# Memory_Chips_5_to_8.net
KiCad netlist of a schematic drawn in Altium Designer
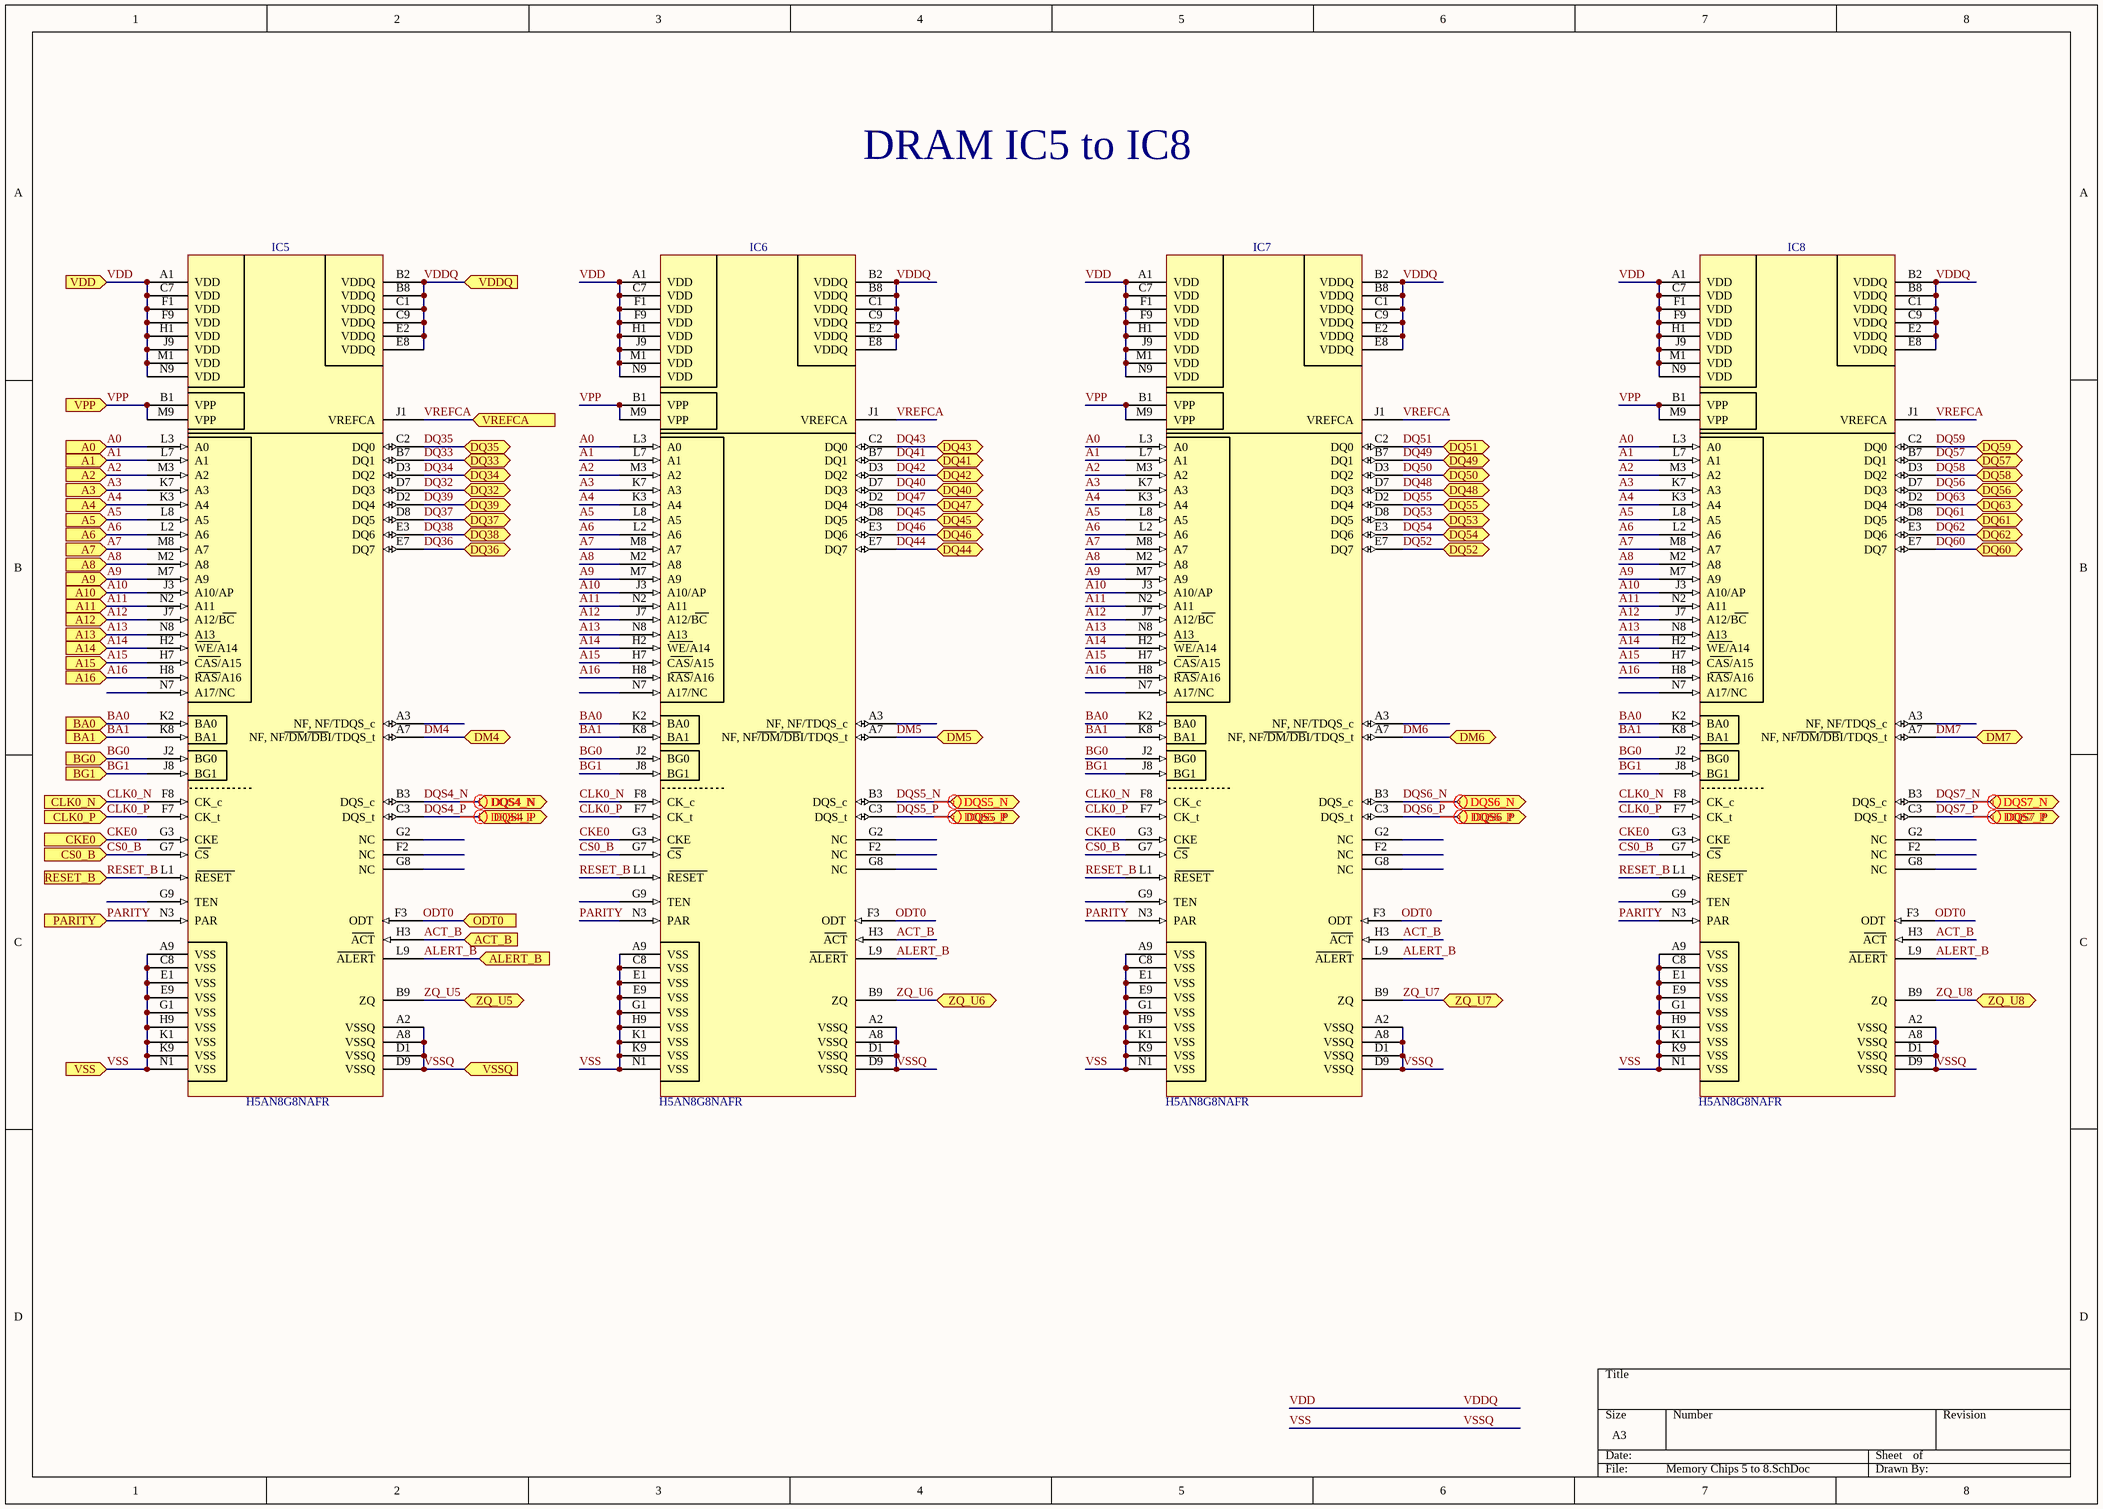
[diagram p0: Memory Chips 5 to 8.SchDoc]

(export (version "E")
  (design (tool "Eeschema 10.0.6"))
  (components
    (comp (ref "IC5")
      (value "H5AN8G8NAFR")
      (footprint "H5AN8G8NAFR")
      (libsource (lib "RouterIntLib") (part "H5AN8G8NAFR"))
    )
    (comp (ref "IC6")
      (value "H5AN8G8NAFR")
      (footprint "H5AN8G8NAFR")
      (libsource (lib "RouterIntLib") (part "H5AN8G8NAFR"))
    )
    (comp (ref "IC7")
      (value "H5AN8G8NAFR")
      (footprint "H5AN8G8NAFR")
      (libsource (lib "RouterIntLib") (part "H5AN8G8NAFR"))
    )
    (comp (ref "IC8")
      (value "H5AN8G8NAFR")
      (footprint "H5AN8G8NAFR")
      (libsource (lib "RouterIntLib") (part "H5AN8G8NAFR"))
    )
  )
  (nets
    (net (code "1") (name "/A0") (class "Default")
      (node (ref "IC5") (pin "L3") (pinfunction "A0_L3") (pintype "input"))
      (node (ref "IC6") (pin "L3") (pinfunction "A0_L3") (pintype "input"))
      (node (ref "IC7") (pin "L3") (pinfunction "A0_L3") (pintype "input"))
      (node (ref "IC8") (pin "L3") (pinfunction "A0_L3") (pintype "input"))
    )
    (net (code "2") (name "/A1") (class "Default")
      (node (ref "IC5") (pin "L7") (pinfunction "A1_L7") (pintype "input"))
      (node (ref "IC6") (pin "L7") (pinfunction "A1_L7") (pintype "input"))
      (node (ref "IC7") (pin "L7") (pinfunction "A1_L7") (pintype "input"))
      (node (ref "IC8") (pin "L7") (pinfunction "A1_L7") (pintype "input"))
    )
    (net (code "3") (name "/A2") (class "Default")
      (node (ref "IC5") (pin "M3") (pinfunction "A2_M3") (pintype "input"))
      (node (ref "IC6") (pin "M3") (pinfunction "A2_M3") (pintype "input"))
      (node (ref "IC7") (pin "M3") (pinfunction "A2_M3") (pintype "input"))
      (node (ref "IC8") (pin "M3") (pinfunction "A2_M3") (pintype "input"))
    )
    (net (code "4") (name "/A3") (class "Default")
      (node (ref "IC5") (pin "K7") (pinfunction "A3_K7") (pintype "input"))
      (node (ref "IC6") (pin "K7") (pinfunction "A3_K7") (pintype "input"))
      (node (ref "IC7") (pin "K7") (pinfunction "A3_K7") (pintype "input"))
      (node (ref "IC8") (pin "K7") (pinfunction "A3_K7") (pintype "input"))
    )
    (net (code "5") (name "/A4") (class "Default")
      (node (ref "IC5") (pin "K3") (pinfunction "A4_K3") (pintype "input"))
      (node (ref "IC6") (pin "K3") (pinfunction "A4_K3") (pintype "input"))
      (node (ref "IC7") (pin "K3") (pinfunction "A4_K3") (pintype "input"))
      (node (ref "IC8") (pin "K3") (pinfunction "A4_K3") (pintype "input"))
    )
    (net (code "6") (name "/A5") (class "Default")
      (node (ref "IC5") (pin "L8") (pinfunction "A5_L8") (pintype "input"))
      (node (ref "IC6") (pin "L8") (pinfunction "A5_L8") (pintype "input"))
      (node (ref "IC7") (pin "L8") (pinfunction "A5_L8") (pintype "input"))
      (node (ref "IC8") (pin "L8") (pinfunction "A5_L8") (pintype "input"))
    )
    (net (code "7") (name "/A6") (class "Default")
      (node (ref "IC5") (pin "L2") (pinfunction "A6_L2") (pintype "input"))
      (node (ref "IC6") (pin "L2") (pinfunction "A6_L2") (pintype "input"))
      (node (ref "IC7") (pin "L2") (pinfunction "A6_L2") (pintype "input"))
      (node (ref "IC8") (pin "L2") (pinfunction "A6_L2") (pintype "input"))
    )
    (net (code "8") (name "/A7") (class "Default")
      (node (ref "IC5") (pin "M8") (pinfunction "A7_M8") (pintype "input"))
      (node (ref "IC6") (pin "M8") (pinfunction "A7_M8") (pintype "input"))
      (node (ref "IC7") (pin "M8") (pinfunction "A7_M8") (pintype "input"))
      (node (ref "IC8") (pin "M8") (pinfunction "A7_M8") (pintype "input"))
    )
    (net (code "9") (name "/A8") (class "Default")
      (node (ref "IC5") (pin "M2") (pinfunction "A8_M2") (pintype "input"))
      (node (ref "IC6") (pin "M2") (pinfunction "A8_M2") (pintype "input"))
      (node (ref "IC7") (pin "M2") (pinfunction "A8_M2") (pintype "input"))
      (node (ref "IC8") (pin "M2") (pinfunction "A8_M2") (pintype "input"))
    )
    (net (code "10") (name "/A9") (class "Default")
      (node (ref "IC5") (pin "M7") (pinfunction "A9_M7") (pintype "input"))
      (node (ref "IC6") (pin "M7") (pinfunction "A9_M7") (pintype "input"))
      (node (ref "IC7") (pin "M7") (pinfunction "A9_M7") (pintype "input"))
      (node (ref "IC8") (pin "M7") (pinfunction "A9_M7") (pintype "input"))
    )
    (net (code "11") (name "/A10") (class "Default")
      (node (ref "IC5") (pin "J3") (pinfunction "A10/AP_J3") (pintype "input"))
      (node (ref "IC6") (pin "J3") (pinfunction "A10/AP_J3") (pintype "input"))
      (node (ref "IC7") (pin "J3") (pinfunction "A10/AP_J3") (pintype "input"))
      (node (ref "IC8") (pin "J3") (pinfunction "A10/AP_J3") (pintype "input"))
    )
    (net (code "12") (name "/A11") (class "Default")
      (node (ref "IC5") (pin "N2") (pinfunction "A11_N2") (pintype "input"))
      (node (ref "IC6") (pin "N2") (pinfunction "A11_N2") (pintype "input"))
      (node (ref "IC7") (pin "N2") (pinfunction "A11_N2") (pintype "input"))
      (node (ref "IC8") (pin "N2") (pinfunction "A11_N2") (pintype "input"))
    )
    (net (code "13") (name "/A12") (class "Default")
      (node (ref "IC5") (pin "J7") (pinfunction "A12/BC_J7") (pintype "input"))
      (node (ref "IC6") (pin "J7") (pinfunction "A12/BC_J7") (pintype "input"))
      (node (ref "IC7") (pin "J7") (pinfunction "A12/BC_J7") (pintype "input"))
      (node (ref "IC8") (pin "J7") (pinfunction "A12/BC_J7") (pintype "input"))
    )
    (net (code "14") (name "/A13") (class "Default")
      (node (ref "IC5") (pin "N8") (pinfunction "A13_N8") (pintype "input"))
      (node (ref "IC6") (pin "N8") (pinfunction "A13_N8") (pintype "input"))
      (node (ref "IC7") (pin "N8") (pinfunction "A13_N8") (pintype "input"))
      (node (ref "IC8") (pin "N8") (pinfunction "A13_N8") (pintype "input"))
    )
    (net (code "15") (name "/A14") (class "Default")
      (node (ref "IC5") (pin "H2") (pinfunction "WE/A14_H2") (pintype "input"))
      (node (ref "IC6") (pin "H2") (pinfunction "WE/A14_H2") (pintype "input"))
      (node (ref "IC7") (pin "H2") (pinfunction "WE/A14_H2") (pintype "input"))
      (node (ref "IC8") (pin "H2") (pinfunction "WE/A14_H2") (pintype "input"))
    )
    (net (code "16") (name "/A15") (class "Default")
      (node (ref "IC5") (pin "H7") (pinfunction "CAS/A15_H7") (pintype "input"))
      (node (ref "IC6") (pin "H7") (pinfunction "CAS/A15_H7") (pintype "input"))
      (node (ref "IC7") (pin "H7") (pinfunction "CAS/A15_H7") (pintype "input"))
      (node (ref "IC8") (pin "H7") (pinfunction "CAS/A15_H7") (pintype "input"))
    )
    (net (code "17") (name "/A16") (class "Default")
      (node (ref "IC5") (pin "H8") (pinfunction "RAS/A16_H8") (pintype "input"))
      (node (ref "IC6") (pin "H8") (pinfunction "RAS/A16_H8") (pintype "input"))
      (node (ref "IC7") (pin "H8") (pinfunction "RAS/A16_H8") (pintype "input"))
      (node (ref "IC8") (pin "H8") (pinfunction "RAS/A16_H8") (pintype "input"))
    )
    (net (code "18") (name "/ACT_B") (class "Default")
      (node (ref "IC5") (pin "H3") (pinfunction "ACT_H3") (pintype "input"))
      (node (ref "IC6") (pin "H3") (pinfunction "ACT_H3") (pintype "input"))
      (node (ref "IC7") (pin "H3") (pinfunction "ACT_H3") (pintype "input"))
      (node (ref "IC8") (pin "H3") (pinfunction "ACT_H3") (pintype "input"))
    )
    (net (code "19") (name "/ALERT_B") (class "Default")
      (node (ref "IC5") (pin "L9") (pinfunction "ALERT_L9") (pintype "passive"))
      (node (ref "IC6") (pin "L9") (pinfunction "ALERT_L9") (pintype "passive"))
      (node (ref "IC7") (pin "L9") (pinfunction "ALERT_L9") (pintype "passive"))
      (node (ref "IC8") (pin "L9") (pinfunction "ALERT_L9") (pintype "passive"))
    )
    (net (code "20") (name "/BA0") (class "Default")
      (node (ref "IC5") (pin "K2") (pinfunction "BA0_K2") (pintype "input"))
      (node (ref "IC6") (pin "K2") (pinfunction "BA0_K2") (pintype "input"))
      (node (ref "IC7") (pin "K2") (pinfunction "BA0_K2") (pintype "input"))
      (node (ref "IC8") (pin "K2") (pinfunction "BA0_K2") (pintype "input"))
    )
    (net (code "21") (name "/BA1") (class "Default")
      (node (ref "IC5") (pin "K8") (pinfunction "BA1_K8") (pintype "input"))
      (node (ref "IC6") (pin "K8") (pinfunction "BA1_K8") (pintype "input"))
      (node (ref "IC7") (pin "K8") (pinfunction "BA1_K8") (pintype "input"))
      (node (ref "IC8") (pin "K8") (pinfunction "BA1_K8") (pintype "input"))
    )
    (net (code "22") (name "/BG0") (class "Default")
      (node (ref "IC5") (pin "J2") (pinfunction "BG0_J2") (pintype "input"))
      (node (ref "IC6") (pin "J2") (pinfunction "BG0_J2") (pintype "input"))
      (node (ref "IC7") (pin "J2") (pinfunction "BG0_J2") (pintype "input"))
      (node (ref "IC8") (pin "J2") (pinfunction "BG0_J2") (pintype "input"))
    )
    (net (code "23") (name "/BG1") (class "Default")
      (node (ref "IC5") (pin "J8") (pinfunction "BG1_J8") (pintype "input"))
      (node (ref "IC6") (pin "J8") (pinfunction "BG1_J8") (pintype "input"))
      (node (ref "IC7") (pin "J8") (pinfunction "BG1_J8") (pintype "input"))
      (node (ref "IC8") (pin "J8") (pinfunction "BG1_J8") (pintype "input"))
    )
    (net (code "24") (name "/CKE0") (class "Default")
      (node (ref "IC5") (pin "G3") (pinfunction "CKE_G3") (pintype "input"))
      (node (ref "IC6") (pin "G3") (pinfunction "CKE_G3") (pintype "input"))
      (node (ref "IC7") (pin "G3") (pinfunction "CKE_G3") (pintype "input"))
      (node (ref "IC8") (pin "G3") (pinfunction "CKE_G3") (pintype "input"))
    )
    (net (code "25") (name "/CLK0_N") (class "Default")
      (node (ref "IC5") (pin "F8") (pinfunction "CK_c_F8") (pintype "input"))
      (node (ref "IC6") (pin "F8") (pinfunction "CK_c_F8") (pintype "input"))
      (node (ref "IC7") (pin "F8") (pinfunction "CK_c_F8") (pintype "input"))
      (node (ref "IC8") (pin "F8") (pinfunction "CK_c_F8") (pintype "input"))
    )
    (net (code "26") (name "/CLK0_P") (class "Default")
      (node (ref "IC5") (pin "F7") (pinfunction "CK_t_F7") (pintype "input"))
      (node (ref "IC6") (pin "F7") (pinfunction "CK_t_F7") (pintype "input"))
      (node (ref "IC7") (pin "F7") (pinfunction "CK_t_F7") (pintype "input"))
      (node (ref "IC8") (pin "F7") (pinfunction "CK_t_F7") (pintype "input"))
    )
    (net (code "27") (name "/CS0_B") (class "Default")
      (node (ref "IC5") (pin "G7") (pinfunction "CS_G7") (pintype "input"))
      (node (ref "IC6") (pin "G7") (pinfunction "CS_G7") (pintype "input"))
      (node (ref "IC7") (pin "G7") (pinfunction "CS_G7") (pintype "input"))
      (node (ref "IC8") (pin "G7") (pinfunction "CS_G7") (pintype "input"))
    )
    (net (code "28") (name "/DM4") (class "Default")
      (node (ref "IC5") (pin "A7") (pinfunction "NF,_NF/DM/DBI/TDQS_t_A7") (pintype "bidirectional"))
    )
    (net (code "29") (name "/DM5") (class "Default")
      (node (ref "IC6") (pin "A7") (pinfunction "NF,_NF/DM/DBI/TDQS_t_A7") (pintype "bidirectional"))
    )
    (net (code "30") (name "/DM6") (class "Default")
      (node (ref "IC7") (pin "A7") (pinfunction "NF,_NF/DM/DBI/TDQS_t_A7") (pintype "bidirectional"))
    )
    (net (code "31") (name "/DM7") (class "Default")
      (node (ref "IC8") (pin "A7") (pinfunction "NF,_NF/DM/DBI/TDQS_t_A7") (pintype "bidirectional"))
    )
    (net (code "32") (name "/DQ32") (class "Default")
      (node (ref "IC5") (pin "D7") (pinfunction "DQ3_D7") (pintype "bidirectional"))
    )
    (net (code "33") (name "/DQ33") (class "Default")
      (node (ref "IC5") (pin "B7") (pinfunction "DQ1_B7") (pintype "bidirectional"))
    )
    (net (code "34") (name "/DQ34") (class "Default")
      (node (ref "IC5") (pin "D3") (pinfunction "DQ2_D3") (pintype "bidirectional"))
    )
    (net (code "35") (name "/DQ35") (class "Default")
      (node (ref "IC5") (pin "C2") (pinfunction "DQ0_C2") (pintype "bidirectional"))
    )
    (net (code "36") (name "/DQ36") (class "Default")
      (node (ref "IC5") (pin "E7") (pinfunction "DQ7_E7") (pintype "bidirectional"))
    )
    (net (code "37") (name "/DQ37") (class "Default")
      (node (ref "IC5") (pin "D8") (pinfunction "DQ5_D8") (pintype "bidirectional"))
    )
    (net (code "38") (name "/DQ38") (class "Default")
      (node (ref "IC5") (pin "E3") (pinfunction "DQ6_E3") (pintype "bidirectional"))
    )
    (net (code "39") (name "/DQ39") (class "Default")
      (node (ref "IC5") (pin "D2") (pinfunction "DQ4_D2") (pintype "bidirectional"))
    )
    (net (code "40") (name "/DQ40") (class "Default")
      (node (ref "IC6") (pin "D7") (pinfunction "DQ3_D7") (pintype "bidirectional"))
    )
    (net (code "41") (name "/DQ41") (class "Default")
      (node (ref "IC6") (pin "B7") (pinfunction "DQ1_B7") (pintype "bidirectional"))
    )
    (net (code "42") (name "/DQ42") (class "Default")
      (node (ref "IC6") (pin "D3") (pinfunction "DQ2_D3") (pintype "bidirectional"))
    )
    (net (code "43") (name "/DQ43") (class "Default")
      (node (ref "IC6") (pin "C2") (pinfunction "DQ0_C2") (pintype "bidirectional"))
    )
    (net (code "44") (name "/DQ44") (class "Default")
      (node (ref "IC6") (pin "E7") (pinfunction "DQ7_E7") (pintype "bidirectional"))
    )
    (net (code "45") (name "/DQ45") (class "Default")
      (node (ref "IC6") (pin "D8") (pinfunction "DQ5_D8") (pintype "bidirectional"))
    )
    (net (code "46") (name "/DQ46") (class "Default")
      (node (ref "IC6") (pin "E3") (pinfunction "DQ6_E3") (pintype "bidirectional"))
    )
    (net (code "47") (name "/DQ47") (class "Default")
      (node (ref "IC6") (pin "D2") (pinfunction "DQ4_D2") (pintype "bidirectional"))
    )
    (net (code "48") (name "/DQ48") (class "Default")
      (node (ref "IC7") (pin "D7") (pinfunction "DQ3_D7") (pintype "bidirectional"))
    )
    (net (code "49") (name "/DQ49") (class "Default")
      (node (ref "IC7") (pin "B7") (pinfunction "DQ1_B7") (pintype "bidirectional"))
    )
    (net (code "50") (name "/DQ50") (class "Default")
      (node (ref "IC7") (pin "D3") (pinfunction "DQ2_D3") (pintype "bidirectional"))
    )
    (net (code "51") (name "/DQ51") (class "Default")
      (node (ref "IC7") (pin "C2") (pinfunction "DQ0_C2") (pintype "bidirectional"))
    )
    (net (code "52") (name "/DQ52") (class "Default")
      (node (ref "IC7") (pin "E7") (pinfunction "DQ7_E7") (pintype "bidirectional"))
    )
    (net (code "53") (name "/DQ53") (class "Default")
      (node (ref "IC7") (pin "D8") (pinfunction "DQ5_D8") (pintype "bidirectional"))
    )
    (net (code "54") (name "/DQ54") (class "Default")
      (node (ref "IC7") (pin "E3") (pinfunction "DQ6_E3") (pintype "bidirectional"))
    )
    (net (code "55") (name "/DQ55") (class "Default")
      (node (ref "IC7") (pin "D2") (pinfunction "DQ4_D2") (pintype "bidirectional"))
    )
    (net (code "56") (name "/DQ56") (class "Default")
      (node (ref "IC8") (pin "D7") (pinfunction "DQ3_D7") (pintype "bidirectional"))
    )
    (net (code "57") (name "/DQ57") (class "Default")
      (node (ref "IC8") (pin "B7") (pinfunction "DQ1_B7") (pintype "bidirectional"))
    )
    (net (code "58") (name "/DQ58") (class "Default")
      (node (ref "IC8") (pin "D3") (pinfunction "DQ2_D3") (pintype "bidirectional"))
    )
    (net (code "59") (name "/DQ59") (class "Default")
      (node (ref "IC8") (pin "C2") (pinfunction "DQ0_C2") (pintype "bidirectional"))
    )
    (net (code "60") (name "/DQ60") (class "Default")
      (node (ref "IC8") (pin "E7") (pinfunction "DQ7_E7") (pintype "bidirectional"))
    )
    (net (code "61") (name "/DQ61") (class "Default")
      (node (ref "IC8") (pin "D8") (pinfunction "DQ5_D8") (pintype "bidirectional"))
    )
    (net (code "62") (name "/DQ62") (class "Default")
      (node (ref "IC8") (pin "E3") (pinfunction "DQ6_E3") (pintype "bidirectional"))
    )
    (net (code "63") (name "/DQ63") (class "Default")
      (node (ref "IC8") (pin "D2") (pinfunction "DQ4_D2") (pintype "bidirectional"))
    )
    (net (code "64") (name "/DQS4_N") (class "Default")
      (node (ref "IC5") (pin "B3") (pinfunction "DQS_c_B3") (pintype "bidirectional"))
    )
    (net (code "65") (name "/DQS4_P") (class "Default")
      (node (ref "IC5") (pin "C3") (pinfunction "DQS_t_C3") (pintype "bidirectional"))
    )
    (net (code "66") (name "/DQS5_N") (class "Default")
      (node (ref "IC6") (pin "B3") (pinfunction "DQS_c_B3") (pintype "bidirectional"))
    )
    (net (code "67") (name "/DQS5_P") (class "Default")
      (node (ref "IC6") (pin "C3") (pinfunction "DQS_t_C3") (pintype "bidirectional"))
    )
    (net (code "68") (name "/DQS6_N") (class "Default")
      (node (ref "IC7") (pin "B3") (pinfunction "DQS_c_B3") (pintype "bidirectional"))
    )
    (net (code "69") (name "/DQS6_P") (class "Default")
      (node (ref "IC7") (pin "C3") (pinfunction "DQS_t_C3") (pintype "bidirectional"))
    )
    (net (code "70") (name "/DQS7_N") (class "Default")
      (node (ref "IC8") (pin "B3") (pinfunction "DQS_c_B3") (pintype "bidirectional"))
    )
    (net (code "71") (name "/DQS7_P") (class "Default")
      (node (ref "IC8") (pin "C3") (pinfunction "DQS_t_C3") (pintype "bidirectional"))
    )
    (net (code "72") (name "/ODT0") (class "Default")
      (node (ref "IC5") (pin "F3") (pinfunction "ODT_F3") (pintype "input"))
      (node (ref "IC6") (pin "F3") (pinfunction "ODT_F3") (pintype "input"))
      (node (ref "IC7") (pin "F3") (pinfunction "ODT_F3") (pintype "input"))
      (node (ref "IC8") (pin "F3") (pinfunction "ODT_F3") (pintype "input"))
    )
    (net (code "73") (name "/PARITY") (class "Default")
      (node (ref "IC5") (pin "N3") (pinfunction "PAR_N3") (pintype "input"))
      (node (ref "IC6") (pin "N3") (pinfunction "PAR_N3") (pintype "input"))
      (node (ref "IC7") (pin "N3") (pinfunction "PAR_N3") (pintype "input"))
      (node (ref "IC8") (pin "N3") (pinfunction "PAR_N3") (pintype "input"))
    )
    (net (code "74") (name "/RESET_B") (class "Default")
      (node (ref "IC5") (pin "L1") (pinfunction "RESET_L1") (pintype "input"))
      (node (ref "IC6") (pin "L1") (pinfunction "RESET_L1") (pintype "input"))
      (node (ref "IC7") (pin "L1") (pinfunction "RESET_L1") (pintype "input"))
      (node (ref "IC8") (pin "L1") (pinfunction "RESET_L1") (pintype "input"))
    )
    (net (code "75") (name "/VDD") (class "Default")
      (node (ref "IC5") (pin "A1") (pinfunction "VDD_A1") (pintype "power_in"))
      (node (ref "IC5") (pin "B2") (pinfunction "VDDQ_B2") (pintype "power_in"))
      (node (ref "IC5") (pin "B8") (pinfunction "VDDQ_B8") (pintype "power_in"))
      (node (ref "IC5") (pin "C1") (pinfunction "VDDQ_C1") (pintype "power_in"))
      (node (ref "IC5") (pin "C7") (pinfunction "VDD_C7") (pintype "power_in"))
      (node (ref "IC5") (pin "C9") (pinfunction "VDDQ_C9") (pintype "power_in"))
      (node (ref "IC5") (pin "E2") (pinfunction "VDDQ_E2") (pintype "power_in"))
      (node (ref "IC5") (pin "E8") (pinfunction "VDDQ_E8") (pintype "power_in"))
      (node (ref "IC5") (pin "F1") (pinfunction "VDD_F1") (pintype "power_in"))
      (node (ref "IC5") (pin "F9") (pinfunction "VDD_F9") (pintype "power_in"))
      (node (ref "IC5") (pin "H1") (pinfunction "VDD_H1") (pintype "power_in"))
      (node (ref "IC5") (pin "J9") (pinfunction "VDD_J9") (pintype "power_in"))
      (node (ref "IC5") (pin "M1") (pinfunction "VDD_M1") (pintype "power_in"))
      (node (ref "IC5") (pin "N9") (pinfunction "VDD_N9") (pintype "power_in"))
      (node (ref "IC6") (pin "A1") (pinfunction "VDD_A1") (pintype "power_in"))
      (node (ref "IC6") (pin "B2") (pinfunction "VDDQ_B2") (pintype "power_in"))
      (node (ref "IC6") (pin "B8") (pinfunction "VDDQ_B8") (pintype "power_in"))
      (node (ref "IC6") (pin "C1") (pinfunction "VDDQ_C1") (pintype "power_in"))
      (node (ref "IC6") (pin "C7") (pinfunction "VDD_C7") (pintype "power_in"))
      (node (ref "IC6") (pin "C9") (pinfunction "VDDQ_C9") (pintype "power_in"))
      (node (ref "IC6") (pin "E2") (pinfunction "VDDQ_E2") (pintype "power_in"))
      (node (ref "IC6") (pin "E8") (pinfunction "VDDQ_E8") (pintype "power_in"))
      (node (ref "IC6") (pin "F1") (pinfunction "VDD_F1") (pintype "power_in"))
      (node (ref "IC6") (pin "F9") (pinfunction "VDD_F9") (pintype "power_in"))
      (node (ref "IC6") (pin "H1") (pinfunction "VDD_H1") (pintype "power_in"))
      (node (ref "IC6") (pin "J9") (pinfunction "VDD_J9") (pintype "power_in"))
      (node (ref "IC6") (pin "M1") (pinfunction "VDD_M1") (pintype "power_in"))
      (node (ref "IC6") (pin "N9") (pinfunction "VDD_N9") (pintype "power_in"))
      (node (ref "IC7") (pin "A1") (pinfunction "VDD_A1") (pintype "power_in"))
      (node (ref "IC7") (pin "B2") (pinfunction "VDDQ_B2") (pintype "power_in"))
      (node (ref "IC7") (pin "B8") (pinfunction "VDDQ_B8") (pintype "power_in"))
      (node (ref "IC7") (pin "C1") (pinfunction "VDDQ_C1") (pintype "power_in"))
      (node (ref "IC7") (pin "C7") (pinfunction "VDD_C7") (pintype "power_in"))
      (node (ref "IC7") (pin "C9") (pinfunction "VDDQ_C9") (pintype "power_in"))
      (node (ref "IC7") (pin "E2") (pinfunction "VDDQ_E2") (pintype "power_in"))
      (node (ref "IC7") (pin "E8") (pinfunction "VDDQ_E8") (pintype "power_in"))
      (node (ref "IC7") (pin "F1") (pinfunction "VDD_F1") (pintype "power_in"))
      (node (ref "IC7") (pin "F9") (pinfunction "VDD_F9") (pintype "power_in"))
      (node (ref "IC7") (pin "H1") (pinfunction "VDD_H1") (pintype "power_in"))
      (node (ref "IC7") (pin "J9") (pinfunction "VDD_J9") (pintype "power_in"))
      (node (ref "IC7") (pin "M1") (pinfunction "VDD_M1") (pintype "power_in"))
      (node (ref "IC7") (pin "N9") (pinfunction "VDD_N9") (pintype "power_in"))
      (node (ref "IC8") (pin "A1") (pinfunction "VDD_A1") (pintype "power_in"))
      (node (ref "IC8") (pin "B2") (pinfunction "VDDQ_B2") (pintype "power_in"))
      (node (ref "IC8") (pin "B8") (pinfunction "VDDQ_B8") (pintype "power_in"))
      (node (ref "IC8") (pin "C1") (pinfunction "VDDQ_C1") (pintype "power_in"))
      (node (ref "IC8") (pin "C7") (pinfunction "VDD_C7") (pintype "power_in"))
      (node (ref "IC8") (pin "C9") (pinfunction "VDDQ_C9") (pintype "power_in"))
      (node (ref "IC8") (pin "E2") (pinfunction "VDDQ_E2") (pintype "power_in"))
      (node (ref "IC8") (pin "E8") (pinfunction "VDDQ_E8") (pintype "power_in"))
      (node (ref "IC8") (pin "F1") (pinfunction "VDD_F1") (pintype "power_in"))
      (node (ref "IC8") (pin "F9") (pinfunction "VDD_F9") (pintype "power_in"))
      (node (ref "IC8") (pin "H1") (pinfunction "VDD_H1") (pintype "power_in"))
      (node (ref "IC8") (pin "J9") (pinfunction "VDD_J9") (pintype "power_in"))
      (node (ref "IC8") (pin "M1") (pinfunction "VDD_M1") (pintype "power_in"))
      (node (ref "IC8") (pin "N9") (pinfunction "VDD_N9") (pintype "power_in"))
    )
    (net (code "76") (name "/VPP") (class "Default")
      (node (ref "IC5") (pin "B1") (pinfunction "VPP_B1") (pintype "power_in"))
      (node (ref "IC5") (pin "M9") (pinfunction "VPP_M9") (pintype "power_in"))
      (node (ref "IC6") (pin "B1") (pinfunction "VPP_B1") (pintype "power_in"))
      (node (ref "IC6") (pin "M9") (pinfunction "VPP_M9") (pintype "power_in"))
      (node (ref "IC7") (pin "B1") (pinfunction "VPP_B1") (pintype "power_in"))
      (node (ref "IC7") (pin "M9") (pinfunction "VPP_M9") (pintype "power_in"))
      (node (ref "IC8") (pin "B1") (pinfunction "VPP_B1") (pintype "power_in"))
      (node (ref "IC8") (pin "M9") (pinfunction "VPP_M9") (pintype "power_in"))
    )
    (net (code "77") (name "/VREFCA") (class "Default")
      (node (ref "IC5") (pin "J1") (pinfunction "VREFCA_J1") (pintype "power_in"))
      (node (ref "IC6") (pin "J1") (pinfunction "VREFCA_J1") (pintype "power_in"))
      (node (ref "IC7") (pin "J1") (pinfunction "VREFCA_J1") (pintype "power_in"))
      (node (ref "IC8") (pin "J1") (pinfunction "VREFCA_J1") (pintype "power_in"))
    )
    (net (code "78") (name "/VSS") (class "Default")
      (node (ref "IC5") (pin "A2") (pinfunction "VSSQ_A2") (pintype "power_in"))
      (node (ref "IC5") (pin "A8") (pinfunction "VSSQ_A8") (pintype "power_in"))
      (node (ref "IC5") (pin "A9") (pinfunction "VSS_A9") (pintype "passive"))
      (node (ref "IC5") (pin "C8") (pinfunction "VSS_C8") (pintype "passive"))
      (node (ref "IC5") (pin "D1") (pinfunction "VSSQ_D1") (pintype "power_in"))
      (node (ref "IC5") (pin "D9") (pinfunction "VSSQ_D9") (pintype "power_in"))
      (node (ref "IC5") (pin "E1") (pinfunction "VSS_E1") (pintype "passive"))
      (node (ref "IC5") (pin "E9") (pinfunction "VSS_E9") (pintype "passive"))
      (node (ref "IC5") (pin "G1") (pinfunction "VSS_G1") (pintype "passive"))
      (node (ref "IC5") (pin "H9") (pinfunction "VSS_H9") (pintype "passive"))
      (node (ref "IC5") (pin "K1") (pinfunction "VSS_K1") (pintype "passive"))
      (node (ref "IC5") (pin "K9") (pinfunction "VSS_K9") (pintype "passive"))
      (node (ref "IC5") (pin "N1") (pinfunction "VSS_N1") (pintype "passive"))
      (node (ref "IC6") (pin "A2") (pinfunction "VSSQ_A2") (pintype "power_in"))
      (node (ref "IC6") (pin "A8") (pinfunction "VSSQ_A8") (pintype "power_in"))
      (node (ref "IC6") (pin "A9") (pinfunction "VSS_A9") (pintype "passive"))
      (node (ref "IC6") (pin "C8") (pinfunction "VSS_C8") (pintype "passive"))
      (node (ref "IC6") (pin "D1") (pinfunction "VSSQ_D1") (pintype "power_in"))
      (node (ref "IC6") (pin "D9") (pinfunction "VSSQ_D9") (pintype "power_in"))
      (node (ref "IC6") (pin "E1") (pinfunction "VSS_E1") (pintype "passive"))
      (node (ref "IC6") (pin "E9") (pinfunction "VSS_E9") (pintype "passive"))
      (node (ref "IC6") (pin "G1") (pinfunction "VSS_G1") (pintype "passive"))
      (node (ref "IC6") (pin "H9") (pinfunction "VSS_H9") (pintype "passive"))
      (node (ref "IC6") (pin "K1") (pinfunction "VSS_K1") (pintype "passive"))
      (node (ref "IC6") (pin "K9") (pinfunction "VSS_K9") (pintype "passive"))
      (node (ref "IC6") (pin "N1") (pinfunction "VSS_N1") (pintype "passive"))
      (node (ref "IC7") (pin "A2") (pinfunction "VSSQ_A2") (pintype "power_in"))
      (node (ref "IC7") (pin "A8") (pinfunction "VSSQ_A8") (pintype "power_in"))
      (node (ref "IC7") (pin "A9") (pinfunction "VSS_A9") (pintype "passive"))
      (node (ref "IC7") (pin "C8") (pinfunction "VSS_C8") (pintype "passive"))
      (node (ref "IC7") (pin "D1") (pinfunction "VSSQ_D1") (pintype "power_in"))
      (node (ref "IC7") (pin "D9") (pinfunction "VSSQ_D9") (pintype "power_in"))
      (node (ref "IC7") (pin "E1") (pinfunction "VSS_E1") (pintype "passive"))
      (node (ref "IC7") (pin "E9") (pinfunction "VSS_E9") (pintype "passive"))
      (node (ref "IC7") (pin "G1") (pinfunction "VSS_G1") (pintype "passive"))
      (node (ref "IC7") (pin "H9") (pinfunction "VSS_H9") (pintype "passive"))
      (node (ref "IC7") (pin "K1") (pinfunction "VSS_K1") (pintype "passive"))
      (node (ref "IC7") (pin "K9") (pinfunction "VSS_K9") (pintype "passive"))
      (node (ref "IC7") (pin "N1") (pinfunction "VSS_N1") (pintype "passive"))
      (node (ref "IC8") (pin "A2") (pinfunction "VSSQ_A2") (pintype "power_in"))
      (node (ref "IC8") (pin "A8") (pinfunction "VSSQ_A8") (pintype "power_in"))
      (node (ref "IC8") (pin "A9") (pinfunction "VSS_A9") (pintype "passive"))
      (node (ref "IC8") (pin "C8") (pinfunction "VSS_C8") (pintype "passive"))
      (node (ref "IC8") (pin "D1") (pinfunction "VSSQ_D1") (pintype "power_in"))
      (node (ref "IC8") (pin "D9") (pinfunction "VSSQ_D9") (pintype "power_in"))
      (node (ref "IC8") (pin "E1") (pinfunction "VSS_E1") (pintype "passive"))
      (node (ref "IC8") (pin "E9") (pinfunction "VSS_E9") (pintype "passive"))
      (node (ref "IC8") (pin "G1") (pinfunction "VSS_G1") (pintype "passive"))
      (node (ref "IC8") (pin "H9") (pinfunction "VSS_H9") (pintype "passive"))
      (node (ref "IC8") (pin "K1") (pinfunction "VSS_K1") (pintype "passive"))
      (node (ref "IC8") (pin "K9") (pinfunction "VSS_K9") (pintype "passive"))
      (node (ref "IC8") (pin "N1") (pinfunction "VSS_N1") (pintype "passive"))
    )
    (net (code "79") (name "/ZQ_U5") (class "Default")
      (node (ref "IC5") (pin "B9") (pinfunction "ZQ_B9") (pintype "passive"))
    )
    (net (code "80") (name "/ZQ_U6") (class "Default")
      (node (ref "IC6") (pin "B9") (pinfunction "ZQ_B9") (pintype "passive"))
    )
    (net (code "81") (name "/ZQ_U7") (class "Default")
      (node (ref "IC7") (pin "B9") (pinfunction "ZQ_B9") (pintype "passive"))
    )
    (net (code "82") (name "/ZQ_U8") (class "Default")
      (node (ref "IC8") (pin "B9") (pinfunction "ZQ_B9") (pintype "passive"))
    )
    (net (code "83") (name "unconnected-(IC5-A17{slash}NC-PadN7)") (class "Default")
      (node (ref "IC5") (pin "N7") (pinfunction "A17/NC_N7") (pintype "input"))
    )
    (net (code "84") (name "unconnected-(IC5-NC-PadF2)") (class "Default")
      (node (ref "IC5") (pin "F2") (pinfunction "NC_F2") (pintype "passive"))
    )
    (net (code "85") (name "unconnected-(IC5-NC-PadG2)") (class "Default")
      (node (ref "IC5") (pin "G2") (pinfunction "NC_G2") (pintype "passive"))
    )
    (net (code "86") (name "unconnected-(IC5-NC-PadG8)") (class "Default")
      (node (ref "IC5") (pin "G8") (pinfunction "NC_G8") (pintype "passive"))
    )
    (net (code "87") (name "unconnected-(IC5-NF,_NF{slash}TDQS_c-PadA3)") (class "Default")
      (node (ref "IC5") (pin "A3") (pinfunction "NF,_NF/TDQS_c_A3") (pintype "bidirectional"))
    )
    (net (code "88") (name "unconnected-(IC5-TEN-PadG9)") (class "Default")
      (node (ref "IC5") (pin "G9") (pinfunction "TEN_G9") (pintype "input"))
    )
    (net (code "89") (name "unconnected-(IC6-A17{slash}NC-PadN7)") (class "Default")
      (node (ref "IC6") (pin "N7") (pinfunction "A17/NC_N7") (pintype "input"))
    )
    (net (code "90") (name "unconnected-(IC6-NC-PadF2)") (class "Default")
      (node (ref "IC6") (pin "F2") (pinfunction "NC_F2") (pintype "passive"))
    )
    (net (code "91") (name "unconnected-(IC6-NC-PadG2)") (class "Default")
      (node (ref "IC6") (pin "G2") (pinfunction "NC_G2") (pintype "passive"))
    )
    (net (code "92") (name "unconnected-(IC6-NC-PadG8)") (class "Default")
      (node (ref "IC6") (pin "G8") (pinfunction "NC_G8") (pintype "passive"))
    )
    (net (code "93") (name "unconnected-(IC6-NF,_NF{slash}TDQS_c-PadA3)") (class "Default")
      (node (ref "IC6") (pin "A3") (pinfunction "NF,_NF/TDQS_c_A3") (pintype "bidirectional"))
    )
    (net (code "94") (name "unconnected-(IC6-TEN-PadG9)") (class "Default")
      (node (ref "IC6") (pin "G9") (pinfunction "TEN_G9") (pintype "input"))
    )
    (net (code "95") (name "unconnected-(IC7-A17{slash}NC-PadN7)") (class "Default")
      (node (ref "IC7") (pin "N7") (pinfunction "A17/NC_N7") (pintype "input"))
    )
    (net (code "96") (name "unconnected-(IC7-NC-PadF2)") (class "Default")
      (node (ref "IC7") (pin "F2") (pinfunction "NC_F2") (pintype "passive"))
    )
    (net (code "97") (name "unconnected-(IC7-NC-PadG2)") (class "Default")
      (node (ref "IC7") (pin "G2") (pinfunction "NC_G2") (pintype "passive"))
    )
    (net (code "98") (name "unconnected-(IC7-NC-PadG8)") (class "Default")
      (node (ref "IC7") (pin "G8") (pinfunction "NC_G8") (pintype "passive"))
    )
    (net (code "99") (name "unconnected-(IC7-NF,_NF{slash}TDQS_c-PadA3)") (class "Default")
      (node (ref "IC7") (pin "A3") (pinfunction "NF,_NF/TDQS_c_A3") (pintype "bidirectional"))
    )
    (net (code "100") (name "unconnected-(IC7-TEN-PadG9)") (class "Default")
      (node (ref "IC7") (pin "G9") (pinfunction "TEN_G9") (pintype "input"))
    )
    (net (code "101") (name "unconnected-(IC8-A17{slash}NC-PadN7)") (class "Default")
      (node (ref "IC8") (pin "N7") (pinfunction "A17/NC_N7") (pintype "input"))
    )
    (net (code "102") (name "unconnected-(IC8-NC-PadF2)") (class "Default")
      (node (ref "IC8") (pin "F2") (pinfunction "NC_F2") (pintype "passive"))
    )
    (net (code "103") (name "unconnected-(IC8-NC-PadG2)") (class "Default")
      (node (ref "IC8") (pin "G2") (pinfunction "NC_G2") (pintype "passive"))
    )
    (net (code "104") (name "unconnected-(IC8-NC-PadG8)") (class "Default")
      (node (ref "IC8") (pin "G8") (pinfunction "NC_G8") (pintype "passive"))
    )
    (net (code "105") (name "unconnected-(IC8-NF,_NF{slash}TDQS_c-PadA3)") (class "Default")
      (node (ref "IC8") (pin "A3") (pinfunction "NF,_NF/TDQS_c_A3") (pintype "bidirectional"))
    )
    (net (code "106") (name "unconnected-(IC8-TEN-PadG9)") (class "Default")
      (node (ref "IC8") (pin "G9") (pinfunction "TEN_G9") (pintype "input"))
    )
  )
)
